# USB_CON.net
KiCad netlist of a schematic drawn in Altium Designer
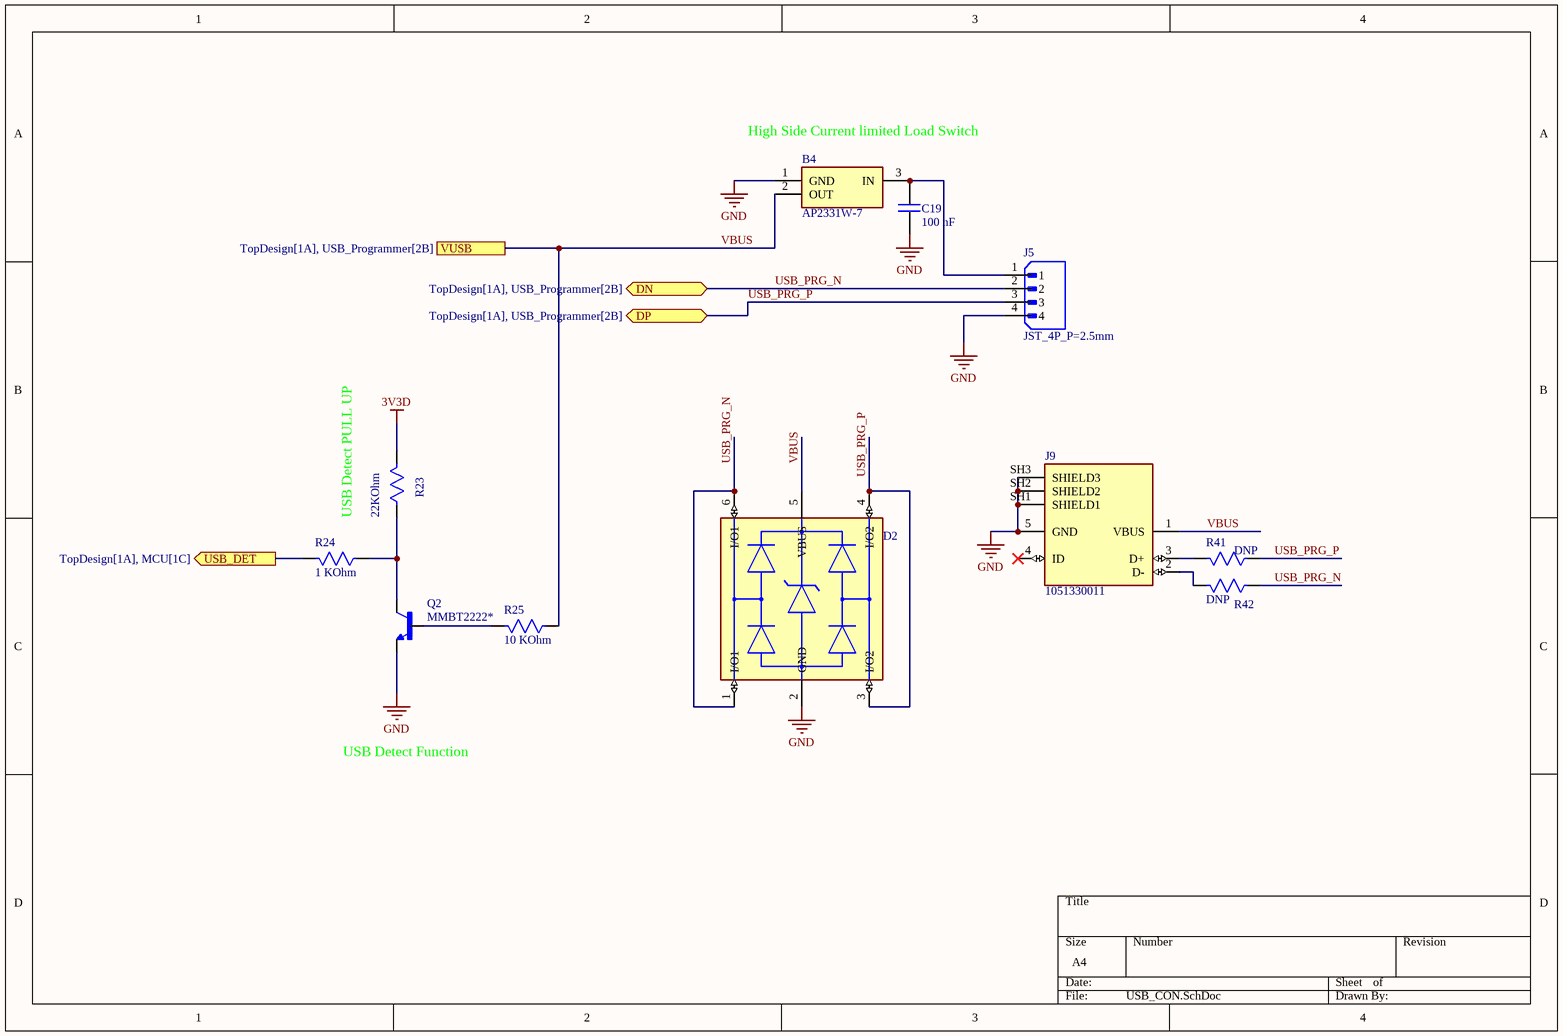
[diagram p0: USB_CON.SchDoc]

(export (version "E")
  (design (tool "Eeschema 10.0.6"))
  (components
    (comp (ref "B4")
      (value "AP2331W-7")
      (footprint "AP2331W-7-(SOT-23-3)")
      (description "High Side Current limited Load Switch 2.7V~5.2V 250mΩ 200mA")
      (libsource (lib "Aptinex_devices") (part "AP2331W-7"))
    )
    (comp (ref "C19")
      (value "100 nF")
      (footprint "CAP_0603")
      (description "Cap SMD.")
      (libsource (lib "Aptinex_discrete") (part "Cap SMD"))
    )
    (comp (ref "D2")
      (value "USBLC6-2SC6")
      (footprint "USBLC6-2SC6")
      (fields (field (name "MPN") "ST Micro Electronics"))
      (libsource (lib "Aptinex_devices") (part "USBLC6-2SC6"))
    )
    (comp (ref "J5")
      (value "JST_4P_P=2.5mm")
      (footprint "JST_4P_Straight_P=2.5mm")
      (description "Connector Header Through Hole 4 position 0.098 (2.50mm)")
      (fields (field (name "MF") "JST Sales") (field (name "MP") "B4B-XH-A(LF)(SN)"))
      (libsource (lib "Aptinex_connectors") (part "JST_4P_P=2.5mm"))
    )
    (comp (ref "J9")
      (value "1051330011")
      (footprint "USB_Micro_B_90_MOLEX_1051330011")
      (description "USB - micro B USB 2.0 Receptacle Connector 5 Position Surface Mount")
      (fields (field (name "MF") "Molex"))
      (libsource (lib "Aptinex_connectors") (part "1051330011"))
    )
    (comp (ref "Q2")
      (value "MMBT2222*")
      (footprint "Bipolar _BJT_ Transistor")
      (description "Bipolar _BJT_ Transistor NPN 30V 600mA 250MHz 350mW Surface Mount SOT-23-3")
      (fields (field (name "MF") "ON Semiconductor") (field (name "MP") "MMBT2222"))
      (libsource (lib "Aptinex_discrete") (part "MMBT2222*"))
    )
    (comp (ref "R23")
      (value "22KOhm")
      (footprint "Res_0603")
      (description "SMD Resistor")
      (fields (field (name "MP") "RC0805FR-07330RL") (field (name "MF") "Yageo"))
      (libsource (lib "Aptinex_discrete") (part "Res smd"))
    )
    (comp (ref "R24")
      (value "1 KOhm")
      (footprint "Res_0603")
      (description "SMD Resistor")
      (fields (field (name "MP") "RC0805FR-07330RL") (field (name "MF") "Yageo"))
      (libsource (lib "Aptinex_discrete") (part "Res smd"))
    )
    (comp (ref "R25")
      (value "10 KOhm")
      (footprint "Res_0603")
      (description "SMD Resistor")
      (fields (field (name "MP") "RC0805FR-07330RL") (field (name "MF") "Yageo"))
      (libsource (lib "Aptinex_discrete") (part "Res smd"))
    )
    (comp (ref "R41")
      (value "DNP")
      (footprint "Res_0603")
      (description "SMD Resistor")
      (fields (field (name "MP") "RC0805FR-07330RL") (field (name "MF") "Yageo"))
      (libsource (lib "Aptinex_discrete") (part "Res smd"))
    )
    (comp (ref "R42")
      (value "DNP")
      (footprint "Res_0603")
      (description "SMD Resistor")
      (fields (field (name "MP") "RC0805FR-07330RL") (field (name "MF") "Yageo"))
      (libsource (lib "Aptinex_discrete") (part "Res smd"))
    )
  )
  (nets
    (net (code "1") (name "/USB_DET") (class "Default")
      (node (ref "R24") (pin "1") (pinfunction "1_1") (pintype "passive"))
    )
    (net (code "2") (name "/USB_PRG_N") (class "Default")
      (node (ref "D2") (pin "1") (pinfunction "I/O1_1") (pintype "bidirectional"))
      (node (ref "D2") (pin "6") (pinfunction "I/O1_6") (pintype "bidirectional"))
      (node (ref "J5") (pin "2") (pinfunction "2_2") (pintype "passive"))
      (node (ref "R42") (pin "2") (pinfunction "2_2") (pintype "passive"))
    )
    (net (code "3") (name "/USB_PRG_P") (class "Default")
      (node (ref "D2") (pin "3") (pinfunction "I/O2_3") (pintype "bidirectional"))
      (node (ref "D2") (pin "4") (pinfunction "I/O2_4") (pintype "bidirectional"))
      (node (ref "J5") (pin "3") (pinfunction "3_3") (pintype "passive"))
      (node (ref "R41") (pin "2") (pinfunction "2_2") (pintype "passive"))
    )
    (net (code "4") (name "/VBUS") (class "Default")
      (node (ref "B4") (pin "2") (pinfunction "OUT_2") (pintype "passive"))
      (node (ref "D2") (pin "5") (pinfunction "VBUS_5") (pintype "power_in"))
      (node (ref "J9") (pin "1") (pinfunction "VBUS_1") (pintype "power_in"))
      (node (ref "R25") (pin "2") (pinfunction "2_2") (pintype "passive"))
    )
    (net (code "5") (name "3V3D") (class "Default")
      (node (ref "R23") (pin "1") (pinfunction "1_1") (pintype "passive"))
    )
    (net (code "6") (name "GND") (class "Default")
      (node (ref "B4") (pin "1") (pinfunction "GND_1") (pintype "passive"))
      (node (ref "C19") (pin "2") (pinfunction "2_2") (pintype "passive"))
      (node (ref "D2") (pin "2") (pinfunction "GND_2") (pintype "power_in"))
      (node (ref "J5") (pin "4") (pinfunction "4_4") (pintype "passive"))
      (node (ref "J9") (pin "5") (pinfunction "GND_5") (pintype "power_in"))
      (node (ref "J9") (pin "SH1") (pinfunction "SHIELD1_SH1") (pintype "passive"))
      (node (ref "J9") (pin "SH2") (pinfunction "SHIELD2_SH2") (pintype "passive"))
      (node (ref "J9") (pin "SH3") (pinfunction "SHIELD3_SH3") (pintype "passive"))
      (node (ref "Q2") (pin "E") (pinfunction "E_E") (pintype "passive"))
    )
    (net (code "7") (name "Net-(B4-IN)") (class "Default")
      (node (ref "B4") (pin "3") (pinfunction "IN_3") (pintype "passive"))
      (node (ref "C19") (pin "1") (pinfunction "1_1") (pintype "passive"))
      (node (ref "J5") (pin "1") (pinfunction "1_1") (pintype "passive"))
    )
    (net (code "8") (name "Net-(J9-D+)") (class "Default")
      (node (ref "J9") (pin "3") (pinfunction "D+_3") (pintype "bidirectional"))
      (node (ref "R41") (pin "1") (pinfunction "1_1") (pintype "passive"))
    )
    (net (code "9") (name "Net-(J9-D-)") (class "Default")
      (node (ref "J9") (pin "2") (pinfunction "D-_2") (pintype "bidirectional"))
      (node (ref "R42") (pin "1") (pinfunction "1_1") (pintype "passive"))
    )
    (net (code "10") (name "Net-(Q2-PadB)") (class "Default")
      (node (ref "Q2") (pin "B") (pinfunction "B_B") (pintype "passive"))
      (node (ref "R25") (pin "1") (pinfunction "1_1") (pintype "passive"))
    )
    (net (code "11") (name "Net-(Q2-PadC)") (class "Default")
      (node (ref "Q2") (pin "C") (pinfunction "C_C") (pintype "passive"))
      (node (ref "R23") (pin "2") (pinfunction "2_2") (pintype "passive"))
      (node (ref "R24") (pin "2") (pinfunction "2_2") (pintype "passive"))
    )
    (net (code "12") (name "unconnected-(J9-ID-Pad4)") (class "Default")
      (node (ref "J9") (pin "4") (pinfunction "ID_4") (pintype "bidirectional+no_connect"))
    )
  )
)
